# Current_Sensor.net
KiCad netlist of a schematic drawn in Altium Designer
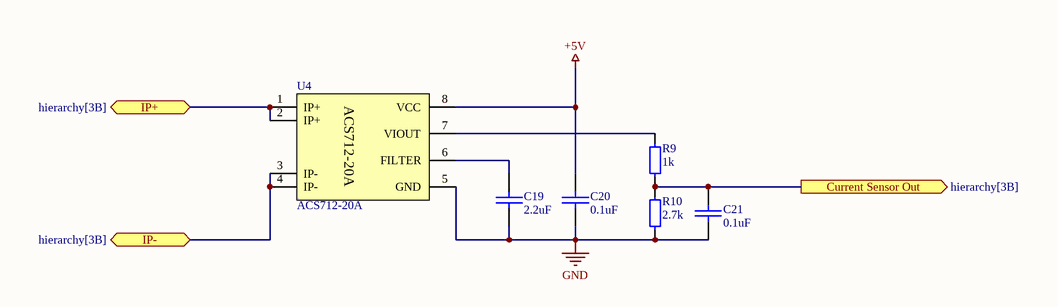
[diagram p0: Current Sensor.SchDoc]

(export (version "E")
  (design (tool "Eeschema 10.0.6"))
  (components
    (comp (ref "C19")
      (value "2.2uF")
      (footprint "0805 Capicator")
      (description "2.2uF X7R 25V 0805")
      (fields
        (field (name "MANUFACTURER") "Murata Manufacturing")
        (field (name "PART NUMBER") "GRM21BR71E225KA73L")
      )
      (libsource (lib "BRT_Components") (part "Cap 2.2uF (0805)"))
    )
    (comp (ref "C20")
      (value "0.1uF")
      (footprint "0805 Capicator")
      (description "0.1uF X7R 25V 10% 0805")
      (fields
        (field (name "MANUFACTURER") "Murata Manufacturing")
        (field (name "PART NUMBER") "GRM21BR71E104KA01L")
      )
      (libsource (lib "BRT_Components") (part "Cap 0.1uF (0805)"))
    )
    (comp (ref "C21")
      (value "0.1uF")
      (footprint "0805 Capicator")
      (description "0.1uF X7R 25V 10% 0805")
      (fields
        (field (name "MANUFACTURER") "Murata Manufacturing")
        (field (name "PART NUMBER") "GRM21BR71E104KA01L")
      )
      (libsource (lib "BRT_Components") (part "Cap 0.1uF (0805)"))
    )
    (comp (ref "R9")
      (value "1k")
      (footprint "0805 Resistor")
      (description "0.125W 0805 1k, 1%")
      (fields (field (name "PART NUMBER") "RC0805FR-071KL") (field (name "MANUFACTURER") "Taiwan"))
      (libsource (lib "BRT_Components") (part "Res 1k (0805)"))
    )
    (comp (ref "R10")
      (value "2.7k")
      (footprint "0805 Resistor")
      (description "0805 0.125W 5% 5.6kOhm")
      (libsource (lib "Altium_Library") (part "Resistor 2.7k (0805)"))
    )
    (comp (ref "U4")
      (value "ACS712-20A")
      (footprint "SOIC-8")
      (libsource (lib "Altium_Library") (part "Current Sensor ACS712-20A"))
    )
  )
  (nets
    (net (code "1") (name "+5V") (class "Default")
      (node (ref "C20") (pin "2") (pinfunction "2_2") (pintype "passive"))
      (node (ref "U4") (pin "8") (pinfunction "VCC_8") (pintype "passive"))
    )
    (net (code "2") (name "/Current Sensor Out") (class "Default")
      (node (ref "C21") (pin "2") (pinfunction "2_2") (pintype "passive"))
      (node (ref "R10") (pin "2") (pinfunction "2_2") (pintype "passive"))
      (node (ref "R9") (pin "1") (pinfunction "1_1") (pintype "passive"))
    )
    (net (code "3") (name "/IP+") (class "Default")
      (node (ref "U4") (pin "1") (pinfunction "IP+_1") (pintype "passive"))
      (node (ref "U4") (pin "2") (pinfunction "IP+_2") (pintype "passive"))
    )
    (net (code "4") (name "/IP-") (class "Default")
      (node (ref "U4") (pin "3") (pinfunction "IP-_3") (pintype "passive"))
      (node (ref "U4") (pin "4") (pinfunction "IP-_4") (pintype "passive"))
    )
    (net (code "5") (name "GND") (class "Default")
      (node (ref "C19") (pin "2") (pinfunction "2_2") (pintype "passive"))
      (node (ref "C20") (pin "1") (pinfunction "1_1") (pintype "passive"))
      (node (ref "C21") (pin "1") (pinfunction "1_1") (pintype "passive"))
      (node (ref "R10") (pin "1") (pinfunction "1_1") (pintype "passive"))
      (node (ref "U4") (pin "5") (pinfunction "GND_5") (pintype "passive"))
    )
    (net (code "6") (name "Net-(U4-FILTER)") (class "Default")
      (node (ref "C19") (pin "1") (pinfunction "1_1") (pintype "passive"))
      (node (ref "U4") (pin "6") (pinfunction "FILTER_6") (pintype "passive"))
    )
    (net (code "7") (name "Net-(U4-VIOUT)") (class "Default")
      (node (ref "R9") (pin "2") (pinfunction "2_2") (pintype "passive"))
      (node (ref "U4") (pin "7") (pinfunction "VIOUT_7") (pintype "passive"))
    )
  )
)
